# CAN_Interface.net
KiCad netlist of a schematic drawn in Altium Designer
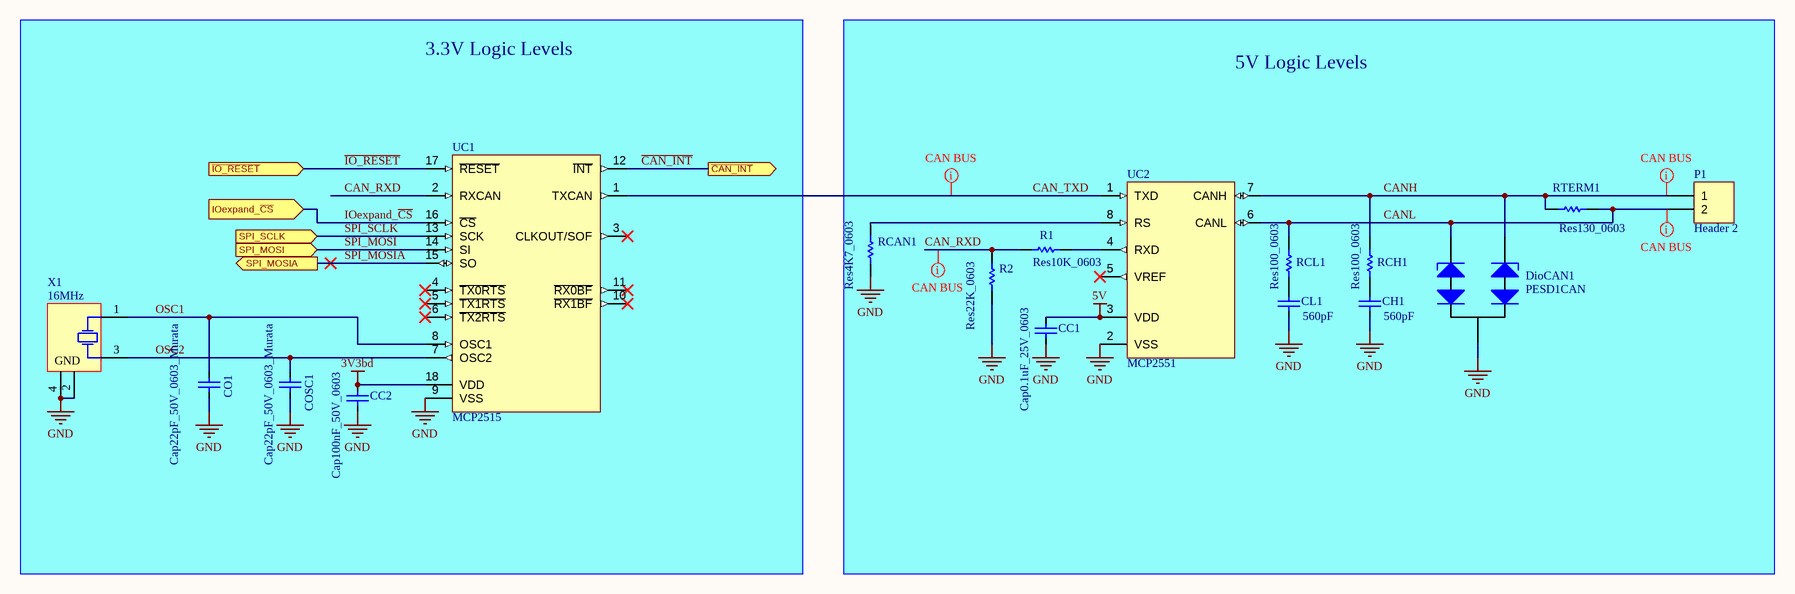
[diagram p0:  CAN_Interface.SchDoc]

(export (version "E")
  (design (tool "Eeschema 10.0.6"))
  (components
    (comp (ref "CC1")
      (value "Cap0.1uF_25V_0603")
      (footprint "0603C_L")
      (libsource (lib "Advanced] Training Course - A365") (part "CAP General"))
    )
    (comp (ref "CC2")
      (value "Cap100nF_50V_0603")
      (footprint "0603C_L")
      (libsource (lib "Advanced] Training Course - A365") (part "CAP General"))
    )
    (comp (ref "CH1")
      (value "560pF")
      (footprint "0603C_L")
      (description "560pF 25V 0603")
      (fields (field (name "Comment") "CAP General"))
      (libsource (lib "Advanced] Training Course - A365") (part "CAP General"))
    )
    (comp (ref "CL1")
      (value "560pF")
      (footprint "0603C_L")
      (description "560pF 25V 0603")
      (fields (field (name "Comment") "CAP General"))
      (libsource (lib "Advanced] Training Course - A365") (part "CAP General"))
    )
    (comp (ref "CO1")
      (value "Cap22pF_50V_0603_Murata")
      (footprint "0603C_L")
      (fields (field (name "TOLERANCE") "5%"))
      (libsource (lib "Advanced] Training Course - A365") (part "CAP General"))
    )
    (comp (ref "COSC1")
      (value "Cap22pF_50V_0603_Murata")
      (footprint "0603C_L")
      (fields (field (name "TOLERANCE") "5%"))
      (libsource (lib "Advanced] Training Course - A365") (part "CAP General"))
    )
    (comp (ref "DioCAN1")
      (value "PESD1CAN")
      (footprint "SOT323")
      (description "Trans Voltage Suppressor Diode, 150W, 24V V(RWM), Bidirectional, 2 Element, Silicon")
      (fields (field (name "MANUFACTURER") "Nexperia USA Inc.") (field (name "SOURCE") "WCT.SchLib"))
      (libsource (lib "Advanced] Training Course - A365") (part "PESD1CAN"))
    )
    (comp (ref "P1")
      (value "Header 2")
      (footprint "HDR1X2")
      (description "Header, 2-Pin")
      (fields (field (name "PUBLISHER") "Altium Limited") (field (name "SOURCE") "WCT.SchLib"))
      (libsource (lib "Advanced] Training Course - A365") (part "Header 2"))
    )
    (comp (ref "R1")
      (value "Res10K_0603")
      (footprint "0603_L")
      (fields
        (field (name "MANUFACTURER") "Panasonic Electronic Components")
        (field (name "MANUFACTURER PART NUMBER") "ERJ-3GEYJ102V")
        (field (name "TOLERANCE") "5%")
        (field (name "SOURCE") "WCT.SchLib")
      )
      (libsource (lib "Advanced] Training Course - A365") (part "Resistor General"))
    )
    (comp (ref "R2")
      (value "Res22K_0603")
      (footprint "0603_L")
      (description "RES22K 0.5% 0603")
      (fields
        (field (name "MANUFACTURER") "Yageo")
        (field (name "MANUFACTURER PART NUMBER") "RT0603DRD0722KL")
        (field (name "SOURCE") "WCT.SchLib")
      )
      (libsource (lib "Advanced] Training Course - A365") (part "Resistor General"))
    )
    (comp (ref "RCAN1")
      (value "Res4K7_0603")
      (footprint "0603_L")
      (fields
        (field (name "MANUFACTURER") "Yageo")
        (field (name "TOLERANCE") "0.5%")
        (field (name "SOURCE") "WCT.SchLib")
      )
      (libsource (lib "Advanced] Training Course - A365") (part "Resistor General"))
    )
    (comp (ref "RCH1")
      (value "Res100_0603")
      (footprint "0603_L")
      (fields
        (field (name "MANUFACTURER") "Panasonic Electronic Components")
        (field (name "TOLERANCE") "5%")
        (field (name "SOURCE") "WCT.SchLib")
      )
      (libsource (lib "Advanced] Training Course - A365") (part "Resistor General"))
    )
    (comp (ref "RCL1")
      (value "Res100_0603")
      (footprint "0603_L")
      (fields
        (field (name "MANUFACTURER") "Panasonic Electronic Components")
        (field (name "TOLERANCE") "5%")
        (field (name "SOURCE") "WCT.SchLib")
      )
      (libsource (lib "Advanced] Training Course - A365") (part "Resistor General"))
    )
    (comp (ref "RTERM1")
      (value "Res130_0603")
      (footprint "0603_L")
      (fields
        (field (name "MANUFACTURER") "Panasonic Electronic Components")
        (field (name "TOLERANCE") "5%")
        (field (name "SOURCE") "WCT.SchLib")
      )
      (libsource (lib "Advanced] Training Course - A365") (part "Resistor General"))
    )
    (comp (ref "UC1")
      (value "MCP2515")
      (footprint "SOIC-SO18_M")
      (description "Stand-Alone CAN Controller With SPI Interface, 18-Pin SOIC, Extended Temperature")
      (fields
        (field (name "MANUFACTURER") "Microchip")
        (field (name "MANUFACTURER PART NUMBER") "MCP2515-E/SO")
        (field (name "AVAILABLE PREVIEW IMAGES") "2D")
        (field (name "SOURCE") "WCT.SchLib")
      )
      (libsource (lib "Advanced] Training Course - A365") (part "MCP2515"))
    )
    (comp (ref "UC2")
      (value "MCP2551")
      (footprint "SOIC-SN8_N")
      (description "High-Speed CAN Transceiver, 8-Pin SOIC, Extended Temperature")
      (fields
        (field (name "MANUFACTURER") "Microchip")
        (field (name "MANUFACTURER PART NUMBER") "MCP2551-E/SN")
        (field (name "AVAILABLE PREVIEW IMAGES") "2D")
        (field (name "SOURCE") "WCT.SchLib")
      )
      (libsource (lib "Advanced] Training Course - A365") (part "MCP2551"))
    )
    (comp (ref "X1")
      (value "CSTCE16M0V53-R0")
      (footprint "FP-ABM8-MFG")
      (description "Crystal 16MHz ±20ppm 18pF SMD-4 3.2mm x 2.5mm CSTCE16M0V53-R0 ABM8-16.000MHZ-B2-T")
      (fields
        (field (name "TOLERANCE") "20ppm")
        (field (name "FREQUENCY") "16MHz")
        (field (name "SOURCE") "WCT.SchLib")
      )
      (libsource (lib " Advanced] Training Course - A365") (part "Crystal 4Pin"))
    )
  )
  (nets
    (net (code "1") (name "/CANH") (class "Default")
      (node (ref "DioCAN1") (pin "1") (pinfunction "A_1") (pintype "passive"))
      (node (ref "P1") (pin "1") (pinfunction "1_1") (pintype "passive"))
      (node (ref "RCH1") (pin "2") (pinfunction "2_2") (pintype "passive"))
      (node (ref "RTERM1") (pin "2") (pinfunction "2_2") (pintype "passive"))
      (node (ref "UC2") (pin "7") (pinfunction "CANH_7") (pintype "bidirectional"))
    )
    (net (code "2") (name "/CANL") (class "Default")
      (node (ref "DioCAN1") (pin "2") (pinfunction "K_2") (pintype "passive"))
      (node (ref "P1") (pin "2") (pinfunction "2_2") (pintype "passive"))
      (node (ref "RCL1") (pin "2") (pinfunction "2_2") (pintype "passive"))
      (node (ref "RTERM1") (pin "1") (pinfunction "1_1") (pintype "passive"))
      (node (ref "UC2") (pin "6") (pinfunction "CANL_6") (pintype "bidirectional"))
    )
    (net (code "3") (name "/CAN_INT") (class "Default")
      (node (ref "UC1") (pin "12") (pinfunction "~{INT}_12") (pintype "output"))
    )
    (net (code "4") (name "/CAN_RXD") (class "Default")
      (node (ref "R1") (pin "2") (pinfunction "2_2") (pintype "passive"))
      (node (ref "R2") (pin "2") (pinfunction "2_2") (pintype "passive"))
      (node (ref "UC1") (pin "2") (pinfunction "RXCAN_2") (pintype "input"))
    )
    (net (code "5") (name "/CAN_TXD") (class "Default")
      (node (ref "UC1") (pin "1") (pinfunction "TXCAN_1") (pintype "output"))
      (node (ref "UC2") (pin "1") (pinfunction "TXD_1") (pintype "input"))
    )
    (net (code "6") (name "/IO_RESET") (class "Default")
      (node (ref "UC1") (pin "17") (pinfunction "~{RESET}_17") (pintype "input"))
    )
    (net (code "7") (name "/IOexpand_~{CS}") (class "Default")
      (node (ref "UC1") (pin "16") (pinfunction "~{CS}_16") (pintype "input"))
    )
    (net (code "8") (name "/OSC1") (class "Default")
      (node (ref "CO1") (pin "2") (pinfunction "2_2") (pintype "passive"))
      (node (ref "UC1") (pin "8") (pinfunction "OSC1_8") (pintype "input"))
      (node (ref "X1") (pin "1") (pinfunction "1_1") (pintype "passive"))
    )
    (net (code "9") (name "/OSC2") (class "Default")
      (node (ref "COSC1") (pin "2") (pinfunction "2_2") (pintype "passive"))
      (node (ref "UC1") (pin "7") (pinfunction "OSC2_7") (pintype "output"))
      (node (ref "X1") (pin "3") (pinfunction "3_3") (pintype "passive"))
    )
    (net (code "10") (name "/SPI_MOSI") (class "Default")
      (node (ref "UC1") (pin "14") (pinfunction "SI_14") (pintype "input"))
    )
    (net (code "11") (name "/SPI_MOSIA") (class "Default")
      (node (ref "UC1") (pin "15") (pinfunction "SO_15") (pintype "bidirectional"))
    )
    (net (code "12") (name "/SPI_SCLK") (class "Default")
      (node (ref "UC1") (pin "13") (pinfunction "SCK_13") (pintype "input"))
    )
    (net (code "13") (name "3V3bd") (class "Default")
      (node (ref "CC2") (pin "2") (pinfunction "2_2") (pintype "passive"))
      (node (ref "UC1") (pin "18") (pinfunction "VDD_18") (pintype "power_in"))
    )
    (net (code "14") (name "5V") (class "Default")
      (node (ref "CC1") (pin "2") (pinfunction "2_2") (pintype "passive"))
      (node (ref "UC2") (pin "3") (pinfunction "VDD_3") (pintype "power_in"))
    )
    (net (code "15") (name "GND") (class "Default")
      (node (ref "CC1") (pin "1") (pinfunction "1_1") (pintype "passive"))
      (node (ref "CC2") (pin "1") (pinfunction "1_1") (pintype "passive"))
      (node (ref "CH1") (pin "2") (pinfunction "2_2") (pintype "passive"))
      (node (ref "CL1") (pin "1") (pinfunction "1_1") (pintype "passive"))
      (node (ref "CO1") (pin "1") (pinfunction "1_1") (pintype "passive"))
      (node (ref "COSC1") (pin "1") (pinfunction "1_1") (pintype "passive"))
      (node (ref "DioCAN1") (pin "3") (pinfunction "3_3") (pintype "passive"))
      (node (ref "R2") (pin "1") (pinfunction "1_1") (pintype "passive"))
      (node (ref "RCAN1") (pin "1") (pinfunction "1_1") (pintype "passive"))
      (node (ref "UC1") (pin "9") (pinfunction "VSS_9") (pintype "power_in"))
      (node (ref "UC2") (pin "2") (pinfunction "VSS_2") (pintype "power_in"))
      (node (ref "X1") (pin "2") (pinfunction "GND_2") (pintype "power_in"))
      (node (ref "X1") (pin "4") (pinfunction "GND_4") (pintype "power_in"))
    )
    (net (code "16") (name "Net-(CH1-Pad1)") (class "Default")
      (node (ref "CH1") (pin "1") (pinfunction "1_1") (pintype "passive"))
      (node (ref "RCH1") (pin "1") (pinfunction "1_1") (pintype "passive"))
    )
    (net (code "17") (name "Net-(CL1-Pad2)") (class "Default")
      (node (ref "CL1") (pin "2") (pinfunction "2_2") (pintype "passive"))
      (node (ref "RCL1") (pin "1") (pinfunction "1_1") (pintype "passive"))
    )
    (net (code "18") (name "Net-(UC2-RS)") (class "Default")
      (node (ref "RCAN1") (pin "2") (pinfunction "2_2") (pintype "passive"))
      (node (ref "UC2") (pin "8") (pinfunction "RS_8") (pintype "input"))
    )
    (net (code "19") (name "Net-(UC2-RXD)") (class "Default")
      (node (ref "R1") (pin "1") (pinfunction "1_1") (pintype "passive"))
      (node (ref "UC2") (pin "4") (pinfunction "RXD_4") (pintype "output"))
    )
    (net (code "20") (name "unconnected-(UC1-CLKOUT{slash}SOF-Pad3)") (class "Default")
      (node (ref "UC1") (pin "3") (pinfunction "CLKOUT/SOF_3") (pintype "output+no_connect"))
    )
    (net (code "21") (name "unconnected-(UC1-~{RX0BF}-Pad11)") (class "Default")
      (node (ref "UC1") (pin "11") (pinfunction "~{RX0BF}_11") (pintype "output+no_connect"))
    )
    (net (code "22") (name "unconnected-(UC1-~{RX1BF}-Pad10)") (class "Default")
      (node (ref "UC1") (pin "10") (pinfunction "~{RX1BF}_10") (pintype "output+no_connect"))
    )
    (net (code "23") (name "unconnected-(UC1-~{TX0RTS}-Pad4)") (class "Default")
      (node (ref "UC1") (pin "4") (pinfunction "~{TX0RTS}_4") (pintype "input+no_connect"))
    )
    (net (code "24") (name "unconnected-(UC1-~{TX1RTS}-Pad5)") (class "Default")
      (node (ref "UC1") (pin "5") (pinfunction "~{TX1RTS}_5") (pintype "input+no_connect"))
    )
    (net (code "25") (name "unconnected-(UC1-~{TX2RTS}-Pad6)") (class "Default")
      (node (ref "UC1") (pin "6") (pinfunction "~{TX2RTS}_6") (pintype "input+no_connect"))
    )
    (net (code "26") (name "unconnected-(UC2-VREF-Pad5)") (class "Default")
      (node (ref "UC2") (pin "5") (pinfunction "VREF_5") (pintype "output+no_connect"))
    )
  )
)
